# Tractive_System_Active_Light_rev6.net
KiCad netlist of a schematic drawn in EAGLE
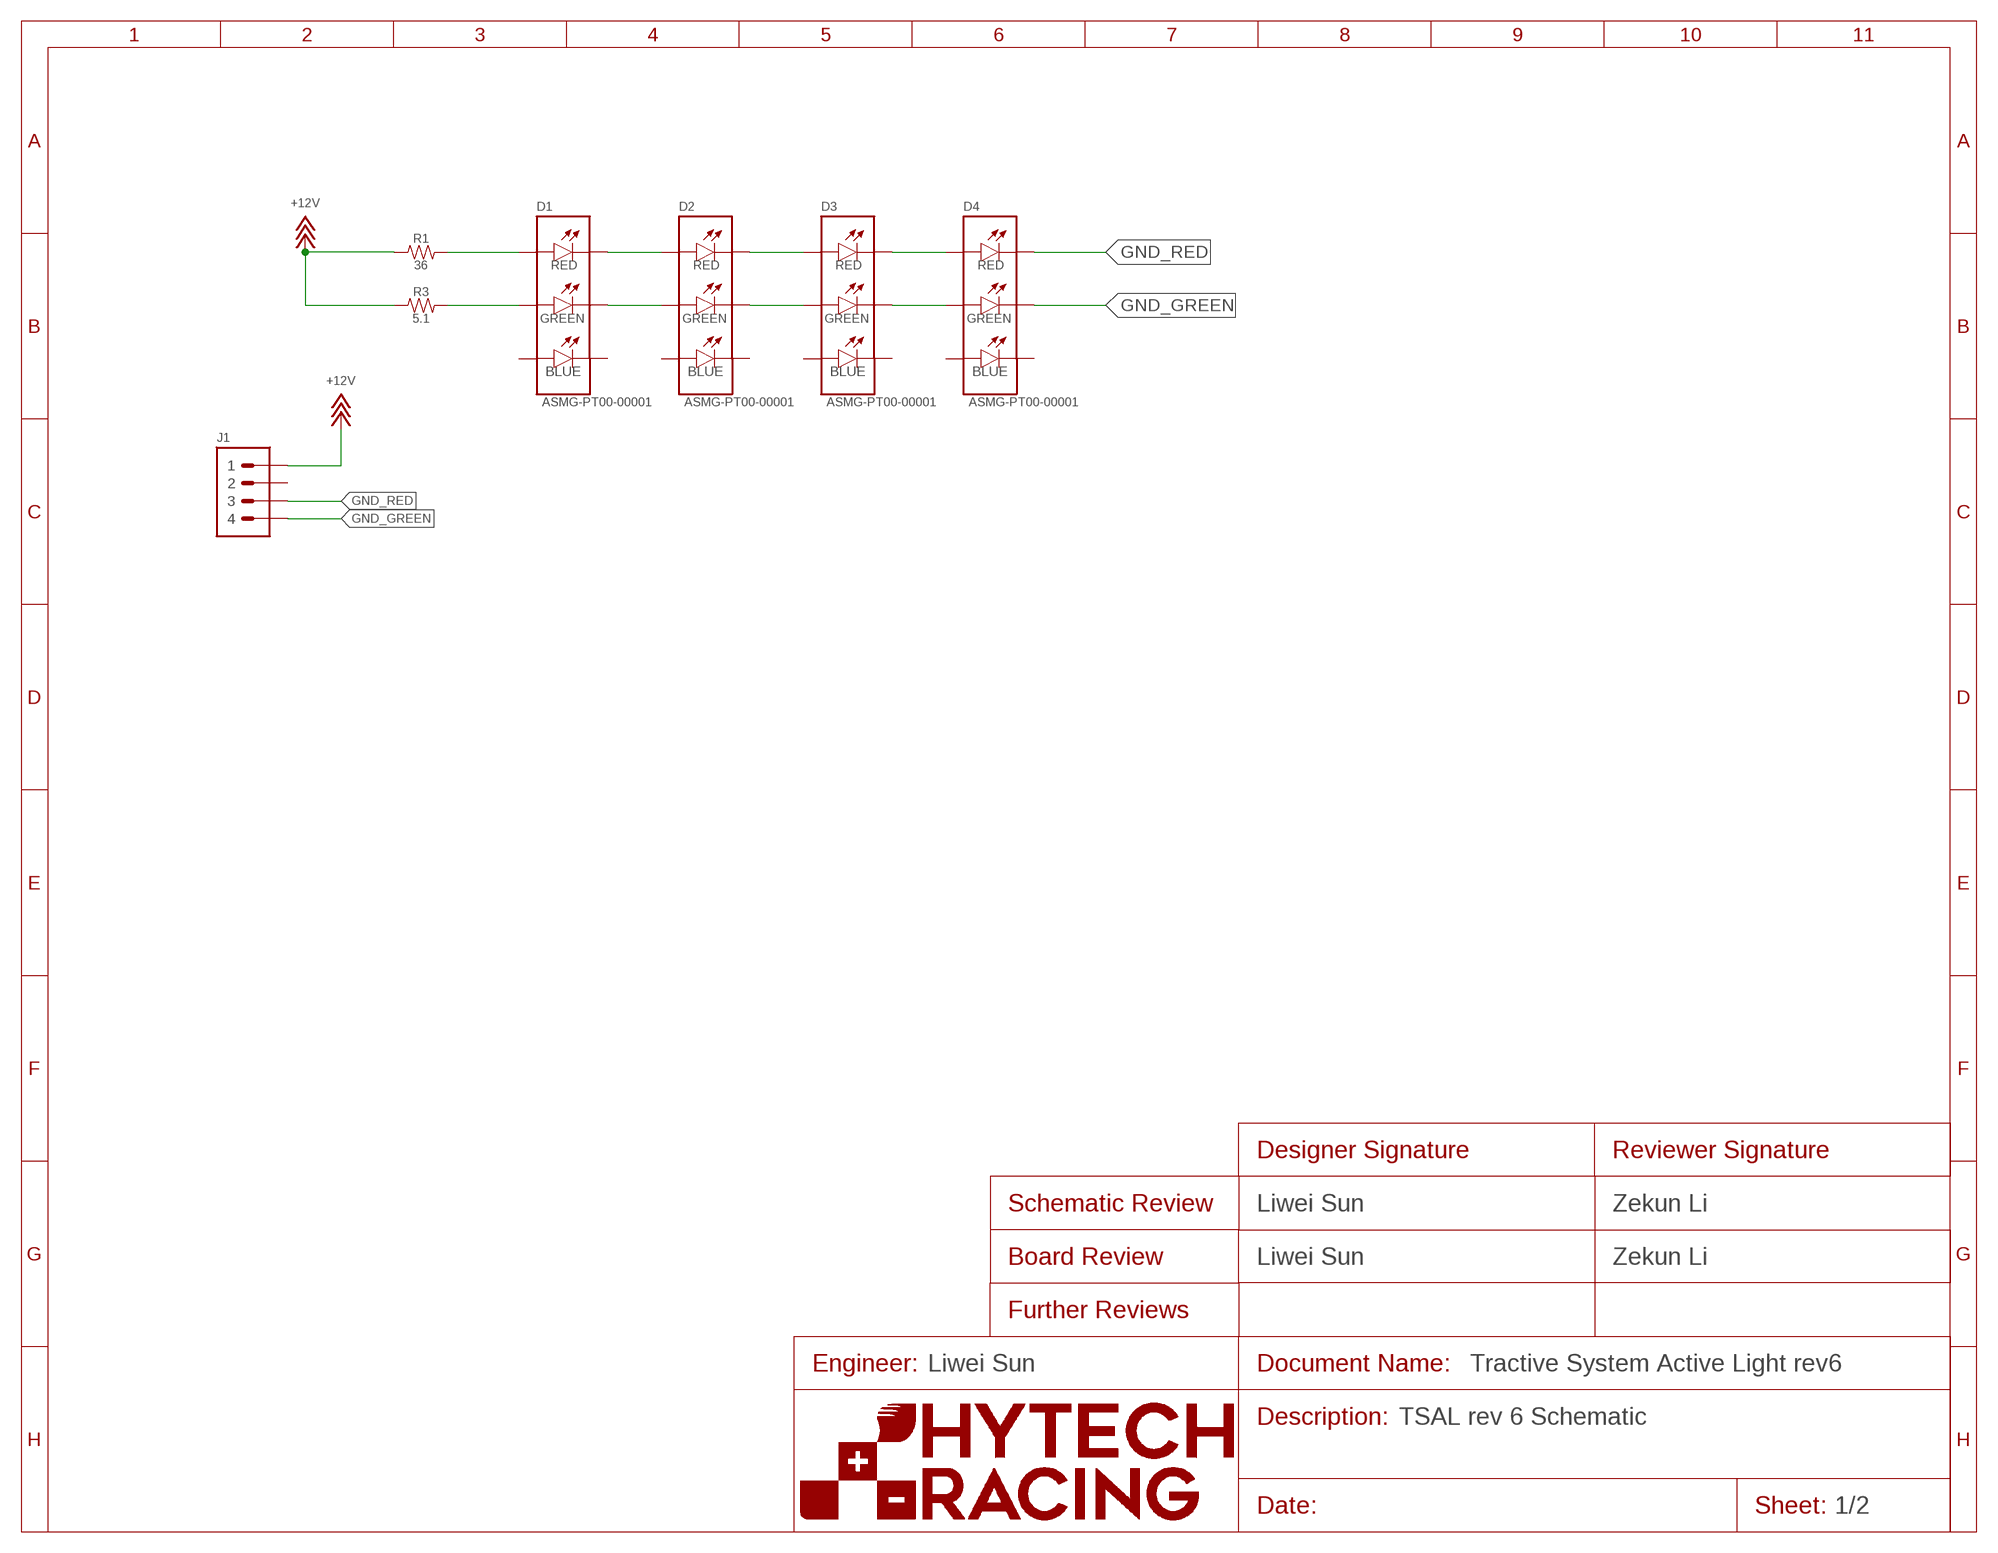
[diagram p0: schematic, sheet 1]
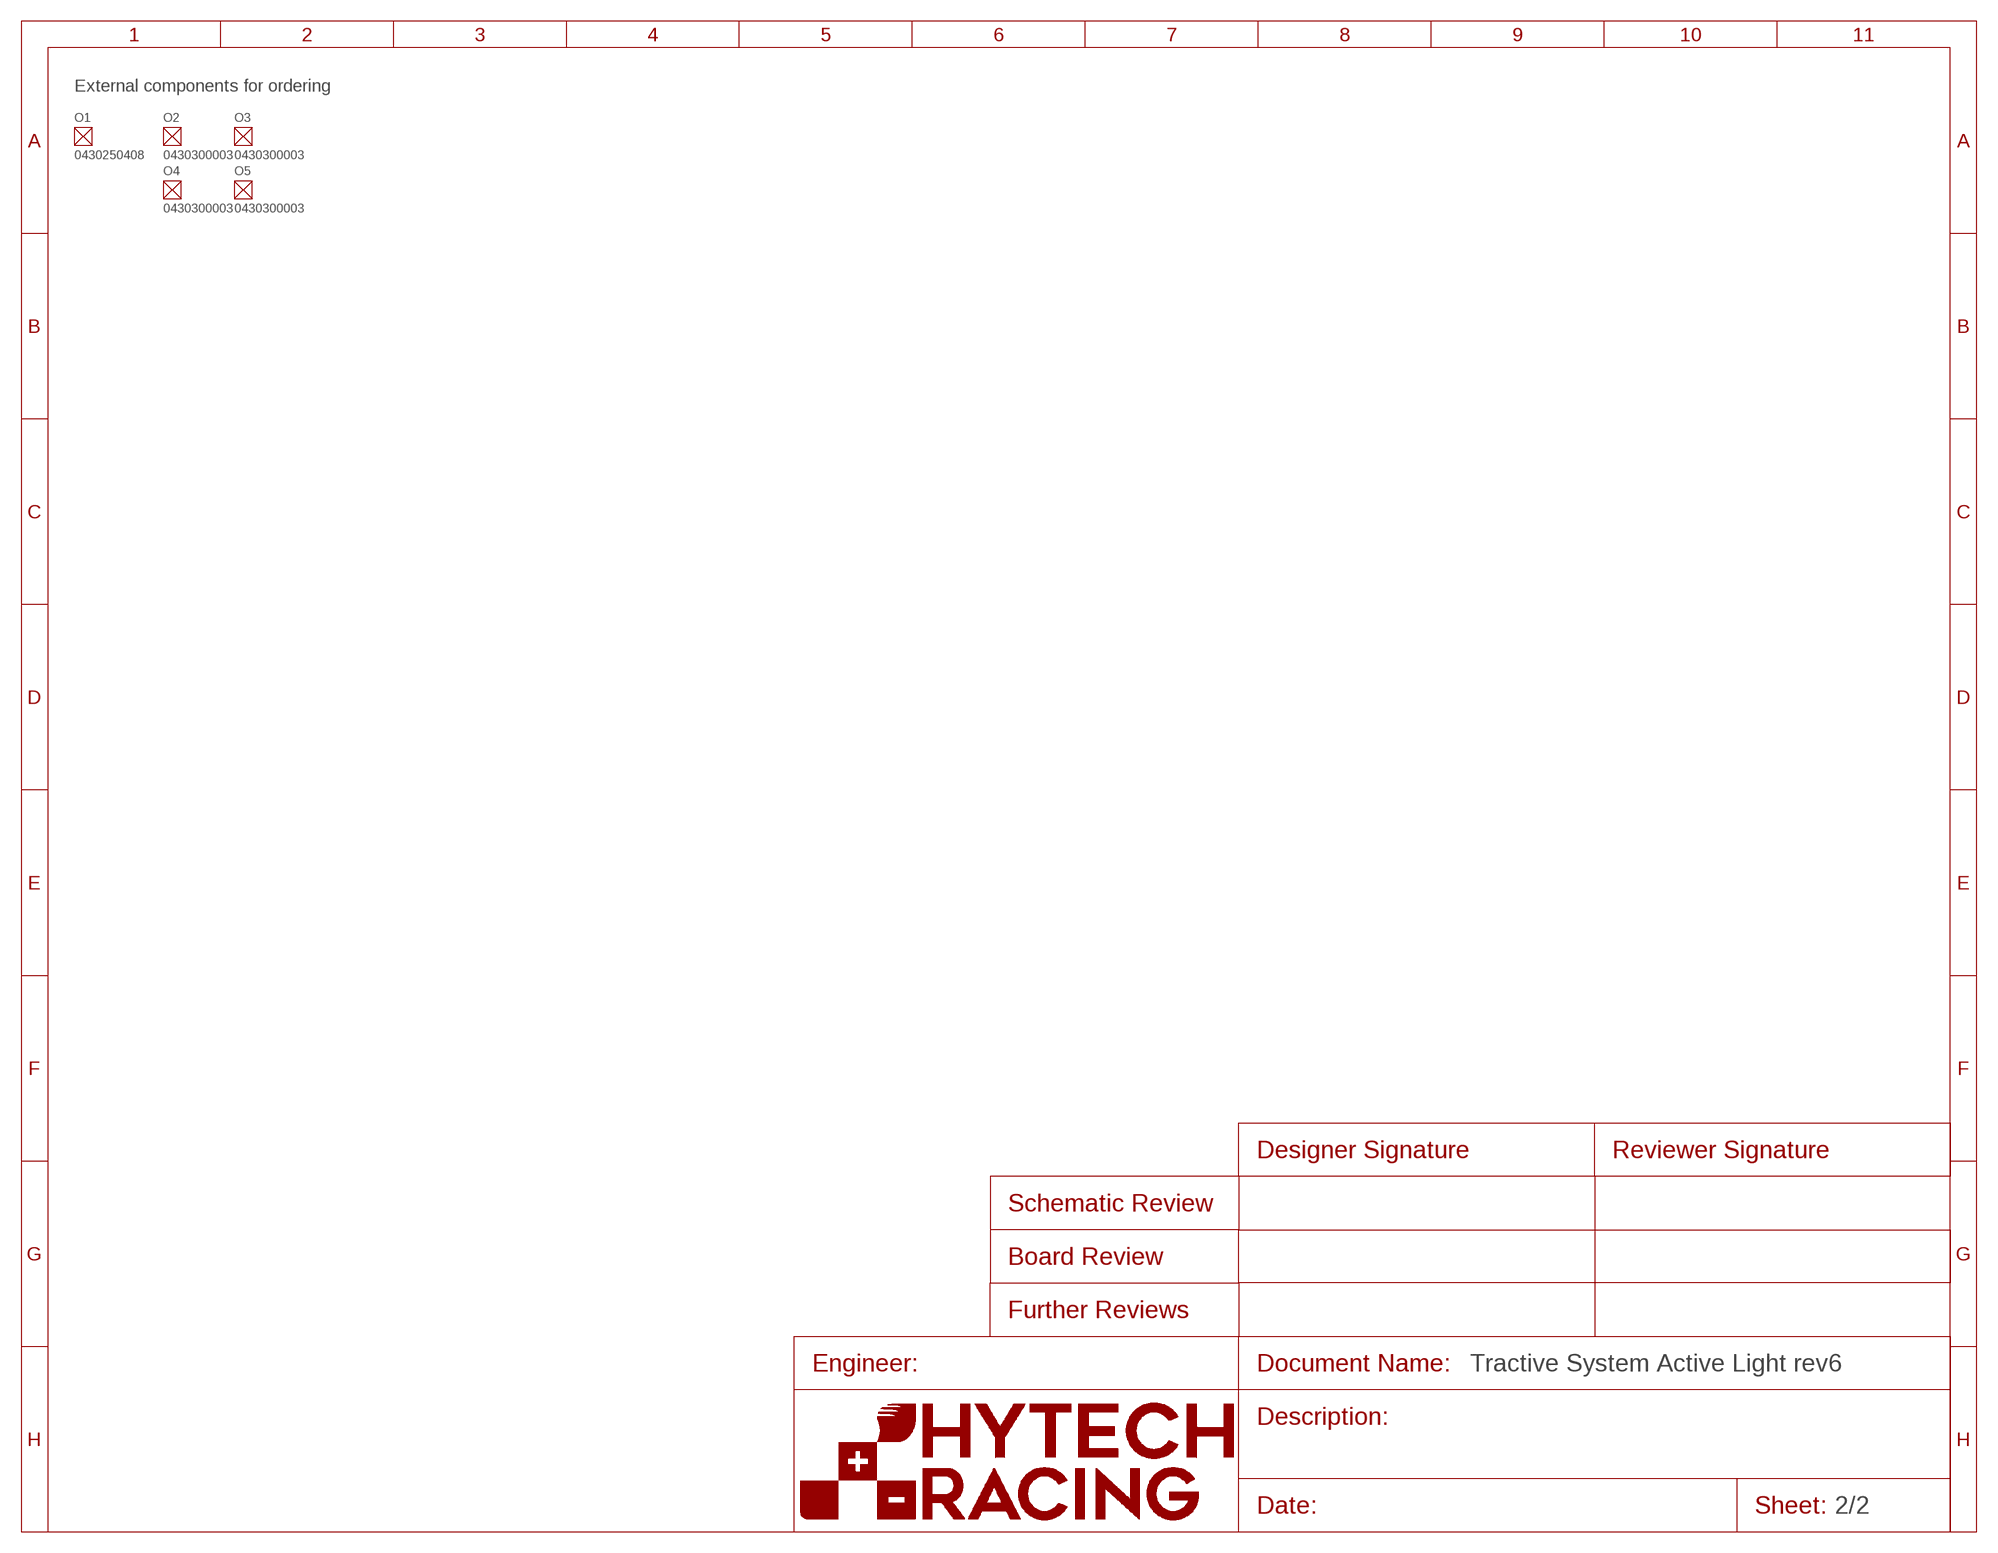
[diagram p1: schematic, sheet 2]

(export (version "E")
  (design (tool "Eeschema 10.0.6"))
  (components
    (comp (ref "D1")
      (value "LED_RGB_ASMG-PT00-00001")
      (footprint "eagle-import:ASMG-PT00-00001")
      (fields (field (name "MANUFACTURER") "Broadcom Limited") (field (name "MPN") "ASMG-PT00-00001"))
      (libsource (lib "eagle-import") (part "LED_RGB_ASMG-PT00-00001"))
    )
    (comp (ref "D2")
      (value "LED_RGB_ASMG-PT00-00001")
      (footprint "eagle-import:ASMG-PT00-00001")
      (fields (field (name "MANUFACTURER") "Broadcom Limited") (field (name "MPN") "ASMG-PT00-00001"))
      (libsource (lib "eagle-import") (part "LED_RGB_ASMG-PT00-00001"))
    )
    (comp (ref "D3")
      (value "LED_RGB_ASMG-PT00-00001")
      (footprint "eagle-import:ASMG-PT00-00001")
      (fields (field (name "MANUFACTURER") "Broadcom Limited") (field (name "MPN") "ASMG-PT00-00001"))
      (libsource (lib "eagle-import") (part "LED_RGB_ASMG-PT00-00001"))
    )
    (comp (ref "D4")
      (value "LED_RGB_ASMG-PT00-00001")
      (footprint "eagle-import:ASMG-PT00-00001")
      (fields (field (name "MANUFACTURER") "Broadcom Limited") (field (name "MPN") "ASMG-PT00-00001"))
      (libsource (lib "eagle-import") (part "LED_RGB_ASMG-PT00-00001"))
    )
    (comp (ref "J1")
      (value "CONNECTOR-4_μF_S_RA_")
      (footprint "eagle-import:MOLEX_MICROFIT_SMD_RIGHTANGLE_04_DUAL")
      (fields (field (name "MPN") "0430450411") (field (name "MANUFACTURER") "Molex"))
      (libsource (lib "eagle-import") (part "CONNECTOR-4_?_μF_S_RA"))
    )
    (comp (ref "R1")
      (value "RESISTOR_0805_36")
      (footprint "eagle-import:0805-RES")
      (fields
        (field (name "MANUFACTURER") "Panasonic Electronic Components")
        (field (name "MPN") "ERJ-P06J360V")
        (field (name "POWER") "0.5W")
        (field (name "RESISTANCE") "36")
      )
      (libsource (lib "eagle-import") (part "RESISTOR_?_080536"))
    )
    (comp (ref "R3")
      (value "RESISTOR_0805_5.1")
      (footprint "eagle-import:0805-RES")
      (fields
        (field (name "MANUFACTURER") "Panasonic Electronic Components")
        (field (name "MPN") "ERJ-6DQJ5R1V")
        (field (name "POWER") "0.5W")
        (field (name "RESISTANCE") "5.1")
      )
      (libsource (lib "eagle-import") (part "RESISTOR_?_08055.1"))
    )
  )
  (nets
    (net (code "1") (name "+12V") (class "Default")
      (node (ref "J1") (pin "1") (pinfunction "1_1") (pintype "passive"))
      (node (ref "R1") (pin "1") (pinfunction "1_1") (pintype "passive"))
      (node (ref "R3") (pin "1") (pinfunction "1_1") (pintype "passive"))
    )
    (net (code "2") (name "GND_GREEN") (class "Default")
      (node (ref "D4") (pin "2") (pinfunction "GREEN-_2") (pintype "passive"))
      (node (ref "J1") (pin "4") (pinfunction "4_4") (pintype "passive"))
    )
    (net (code "3") (name "GND_RED") (class "Default")
      (node (ref "D4") (pin "1") (pinfunction "RED-_1") (pintype "passive"))
      (node (ref "J1") (pin "3") (pinfunction "3_3") (pintype "passive"))
    )
    (net (code "4") (name "Net-(D1-GREEN+)") (class "Default")
      (node (ref "D1") (pin "5") (pinfunction "GREEN+_5") (pintype "passive"))
      (node (ref "R3") (pin "2") (pinfunction "2_2") (pintype "passive"))
    )
    (net (code "5") (name "Net-(D1-GREEN-)") (class "Default")
      (node (ref "D1") (pin "2") (pinfunction "GREEN-_2") (pintype "passive"))
      (node (ref "D2") (pin "5") (pinfunction "GREEN+_5") (pintype "passive"))
    )
    (net (code "6") (name "Net-(D1-RED+-Pad4)") (class "Default")
      (node (ref "D1") (pin "4") (pinfunction "RED+_4") (pintype "passive"))
      (node (ref "D1") (pin "THERMAL") (pinfunction "RED+_THERMAL") (pintype "passive"))
      (node (ref "R1") (pin "2") (pinfunction "2_2") (pintype "passive"))
    )
    (net (code "7") (name "Net-(D1-RED-)") (class "Default")
      (node (ref "D1") (pin "1") (pinfunction "RED-_1") (pintype "passive"))
      (node (ref "D2") (pin "4") (pinfunction "RED+_4") (pintype "passive"))
      (node (ref "D2") (pin "THERMAL") (pinfunction "RED+_THERMAL") (pintype "passive"))
    )
    (net (code "8") (name "Net-(D2-GREEN-)") (class "Default")
      (node (ref "D2") (pin "2") (pinfunction "GREEN-_2") (pintype "passive"))
      (node (ref "D3") (pin "5") (pinfunction "GREEN+_5") (pintype "passive"))
    )
    (net (code "9") (name "Net-(D2-RED-)") (class "Default")
      (node (ref "D2") (pin "1") (pinfunction "RED-_1") (pintype "passive"))
      (node (ref "D3") (pin "4") (pinfunction "RED+_4") (pintype "passive"))
      (node (ref "D3") (pin "THERMAL") (pinfunction "RED+_THERMAL") (pintype "passive"))
    )
    (net (code "10") (name "Net-(D3-GREEN-)") (class "Default")
      (node (ref "D3") (pin "2") (pinfunction "GREEN-_2") (pintype "passive"))
      (node (ref "D4") (pin "5") (pinfunction "GREEN+_5") (pintype "passive"))
    )
    (net (code "11") (name "Net-(D3-RED-)") (class "Default")
      (node (ref "D3") (pin "1") (pinfunction "RED-_1") (pintype "passive"))
      (node (ref "D4") (pin "4") (pinfunction "RED+_4") (pintype "passive"))
      (node (ref "D4") (pin "THERMAL") (pinfunction "RED+_THERMAL") (pintype "passive"))
    )
    (net (code "12") (name "unconnected-(D1-BLUE+-Pad6)") (class "Default")
      (node (ref "D1") (pin "6") (pinfunction "BLUE+_6") (pintype "passive"))
    )
    (net (code "13") (name "unconnected-(D1-BLUE--Pad3)") (class "Default")
      (node (ref "D1") (pin "3") (pinfunction "BLUE-_3") (pintype "passive"))
    )
    (net (code "14") (name "unconnected-(D2-BLUE+-Pad6)") (class "Default")
      (node (ref "D2") (pin "6") (pinfunction "BLUE+_6") (pintype "passive"))
    )
    (net (code "15") (name "unconnected-(D2-BLUE--Pad3)") (class "Default")
      (node (ref "D2") (pin "3") (pinfunction "BLUE-_3") (pintype "passive"))
    )
    (net (code "16") (name "unconnected-(D3-BLUE+-Pad6)") (class "Default")
      (node (ref "D3") (pin "6") (pinfunction "BLUE+_6") (pintype "passive"))
    )
    (net (code "17") (name "unconnected-(D3-BLUE--Pad3)") (class "Default")
      (node (ref "D3") (pin "3") (pinfunction "BLUE-_3") (pintype "passive"))
    )
    (net (code "18") (name "unconnected-(D4-BLUE+-Pad6)") (class "Default")
      (node (ref "D4") (pin "6") (pinfunction "BLUE+_6") (pintype "passive"))
    )
    (net (code "19") (name "unconnected-(D4-BLUE--Pad3)") (class "Default")
      (node (ref "D4") (pin "3") (pinfunction "BLUE-_3") (pintype "passive"))
    )
    (net (code "20") (name "unconnected-(J1-Pad2)") (class "Default")
      (node (ref "J1") (pin "2") (pinfunction "2_2") (pintype "passive"))
    )
  )
)
